# Filter_R.net
KiCad netlist of a schematic drawn in Altium Designer
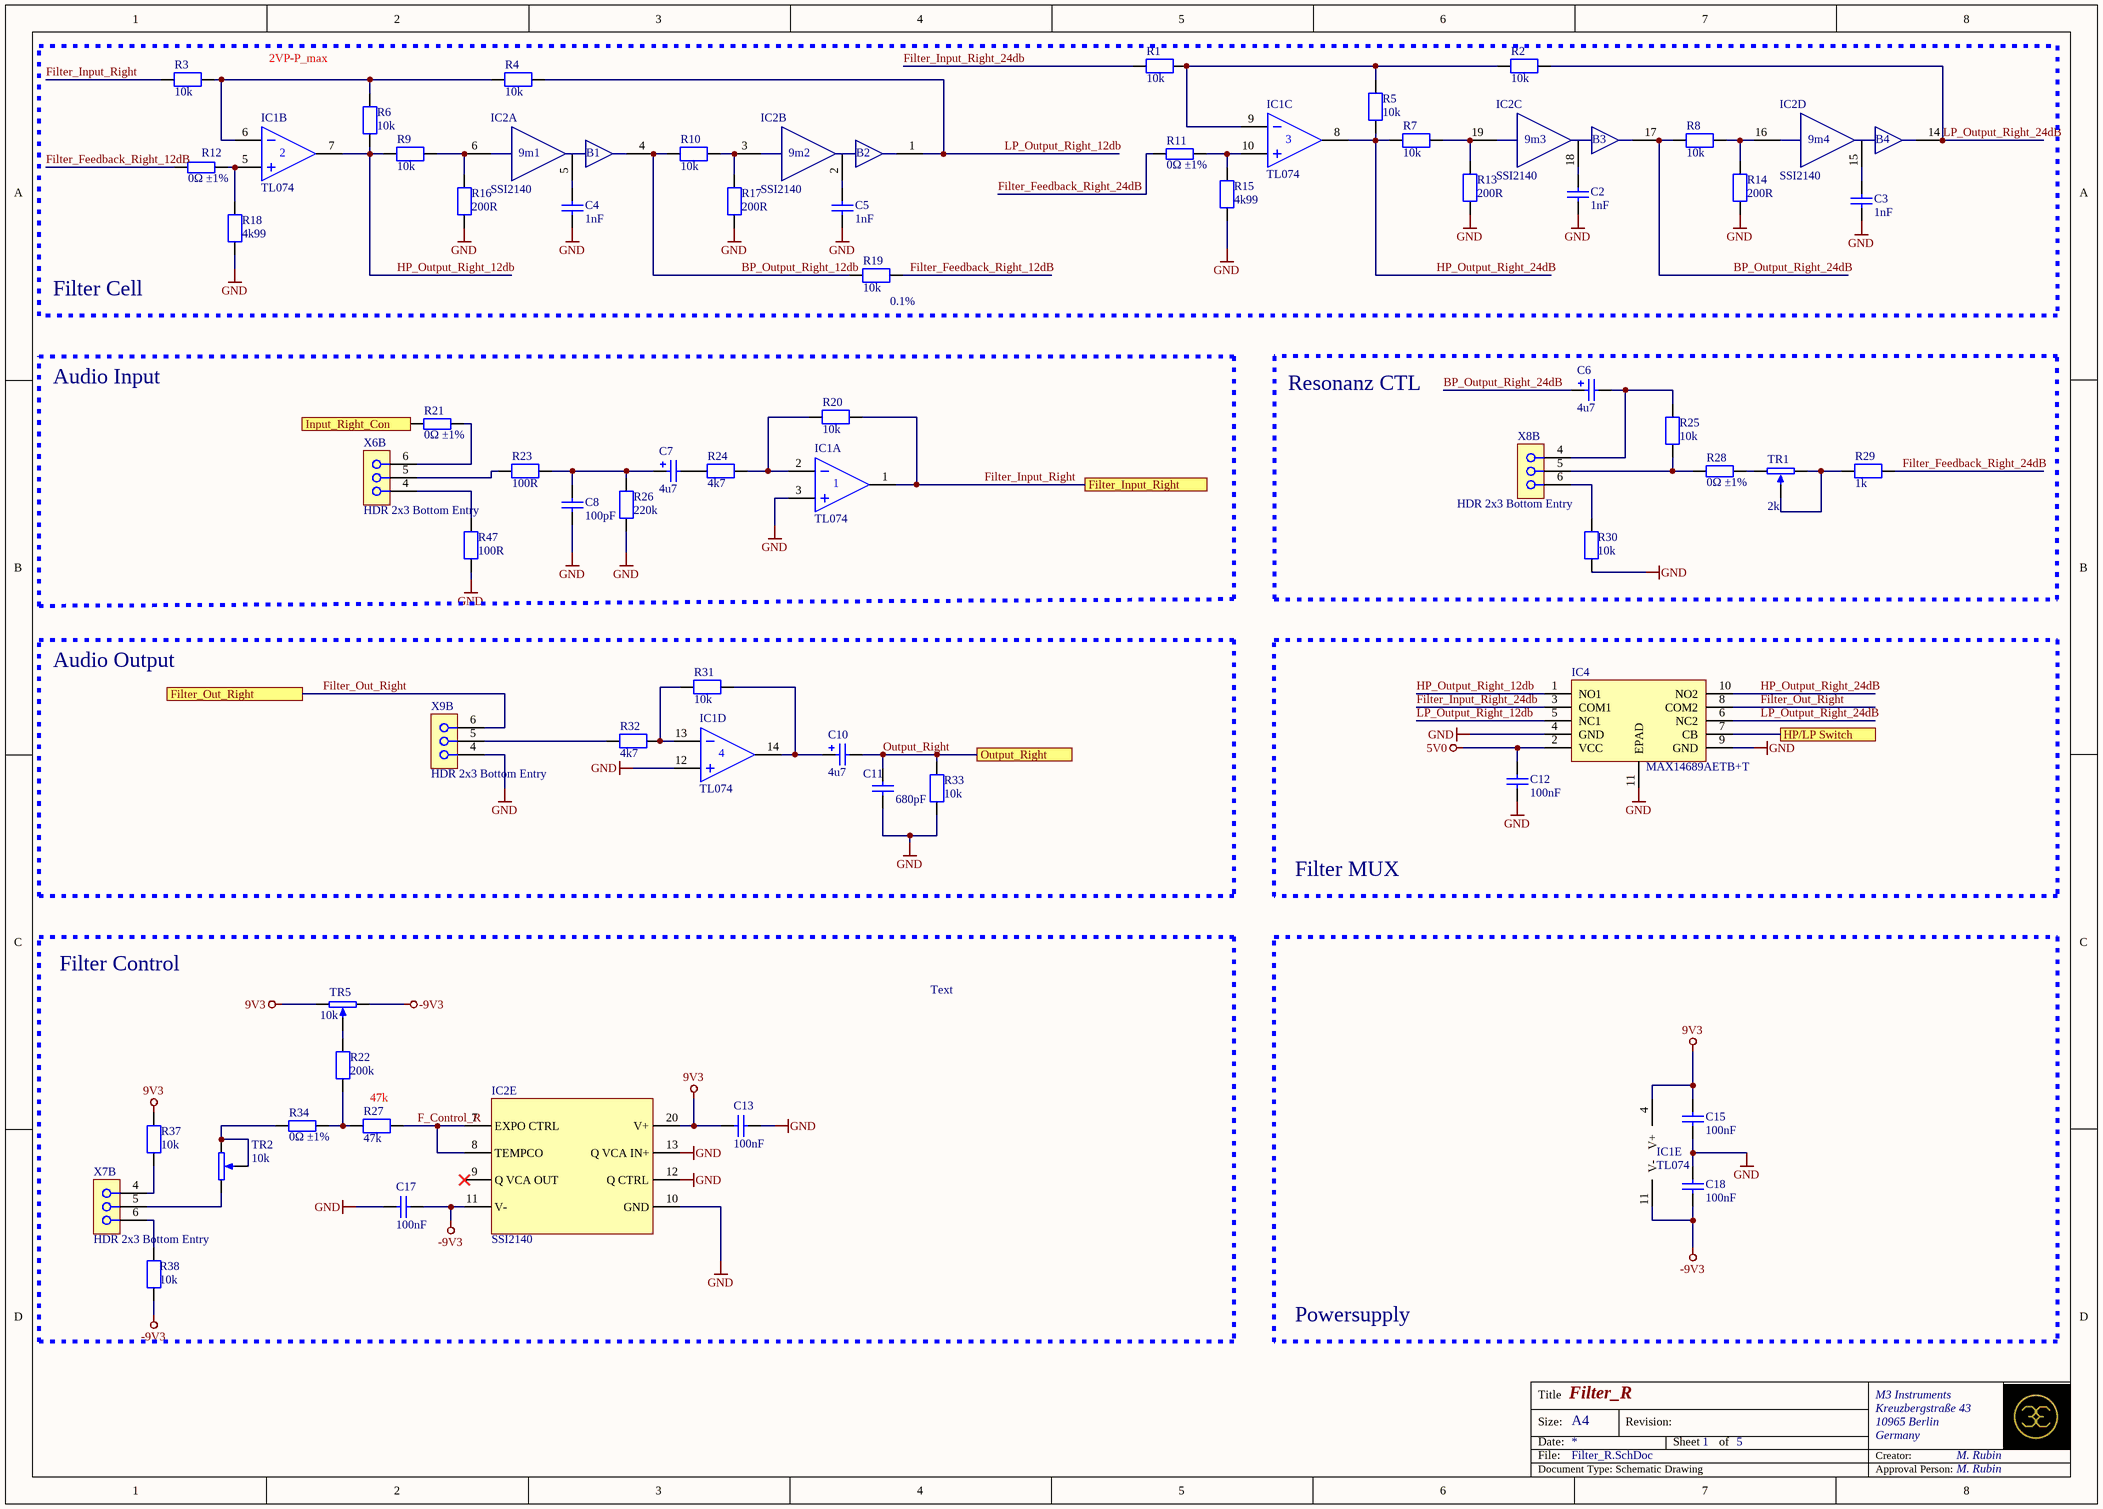
[diagram p0: Filter_R.SchDoc]

(export (version "E")
  (design (tool "Eeschema 10.0.6"))
  (components
    (comp (ref "C2")
      (value "1nF")
      (footprint "CAPC2012X145N")
      (description "Multilayer Ceramic Capacitors MLCC - SMD/SMT, C0G(NP0), 100nF")
      (fields
        (field (name "MANUFACTURER") "Murata Electronics")
        (field (name "MANUFACTURER PART NUMBER") "GRM21B5C2J102JWA3L")
      )
      (libsource (lib "Caps") (part "CAP_1nF_630V"))
    )
    (comp (ref "C3")
      (value "1nF")
      (footprint "CAPC2012X145N")
      (description "Multilayer Ceramic Capacitors MLCC - SMD/SMT, C0G(NP0), 1nF")
      (fields
        (field (name "MANUFACTURER") "Murata Electronics")
        (field (name "MANUFACTURER PART NUMBER") "GRM21B5C2J102JWA3L")
      )
      (libsource (lib "Caps") (part "CAP_100nF_630V"))
    )
    (comp (ref "C4")
      (value "1nF")
      (footprint "CAPC2012X145N")
      (description "Multilayer Ceramic Capacitors MLCC - SMD/SMT, C0G(NP0), 100nF")
      (fields
        (field (name "MANUFACTURER") "Murata Electronics")
        (field (name "MANUFACTURER PART NUMBER") "GRM21B5C2J102JWA3L")
      )
      (libsource (lib "Caps") (part "CAP_1nF_630V"))
    )
    (comp (ref "C5")
      (value "1nF")
      (footprint "CAPC2012X145N")
      (description "Multilayer Ceramic Capacitors MLCC - SMD/SMT, C0G(NP0), 1nF")
      (fields
        (field (name "MANUFACTURER") "Murata Electronics")
        (field (name "MANUFACTURER PART NUMBER") "GRM21B5C2J102JWA3L")
      )
      (libsource (lib "Caps") (part "CAP_100nF_630V"))
    )
    (comp (ref "C6")
      (value "4u7")
      (footprint "CAPAE4643X54M")
      (description "Aluminium Electrolytic Capacitors - SMD 4.7UF 16V ELECT VS BI-POLAR")
      (fields
        (field (name "MANUFACTURER") "Panasonic")
        (field (name "MANUFACTURER PART NUMBER") "EEE-1CA4R7NR")
      )
      (libsource (lib "Caps") (part "CAP_4u7"))
    )
    (comp (ref "C7")
      (value "4u7")
      (footprint "CAPAE4643X54M")
      (description "Aluminium Electrolytic Capacitors - SMD 4.7UF 16V ELECT VS BI-POLAR")
      (fields
        (field (name "MANUFACTURER") "Panasonic")
        (field (name "MANUFACTURER PART NUMBER") "EEE-1CA4R7NR")
      )
      (libsource (lib "Caps") (part "CAP_4u7"))
    )
    (comp (ref "C8")
      (value "100pF")
      (footprint "CAPC2012X145N")
      (description "Film Capacitors 100pF 50VDC 2% PPS FILM 0805")
      (fields
        (field (name "MANUFACTURER") "Panasonic")
        (field (name "MANUFACTURER PART NUMBER") "ECH-U1H101GX5")
      )
      (libsource (lib "Caps") (part "CAP_100pF_0805"))
    )
    (comp (ref "C10")
      (value "4u7")
      (footprint "CAPAE4643X54M")
      (description "Aluminium Electrolytic Capacitors - SMD 4.7UF 16V ELECT VS BI-POLAR")
      (fields
        (field (name "MANUFACTURER") "Panasonic")
        (field (name "MANUFACTURER PART NUMBER") "EEE-1CA4R7NR")
      )
      (libsource (lib "Caps") (part "CAP_4u7"))
    )
    (comp (ref "C11")
      (value "680pF")
      (footprint "CAPC2012X145N")
      (description "Film Capacitors 680pF 50VDC 2% PPS FILM 0805")
      (fields
        (field (name "MANUFACTURER") "Panasonic")
        (field (name "MANUFACTURER PART NUMBER") "ECH-U1H681GX5")
      )
      (libsource (lib "Caps") (part "CAP_680pF_0805"))
    )
    (comp (ref "C12")
      (value "100nF")
      (footprint "CAPC1608X95N")
      (description "Multilayer Ceramic Capacitors MLCC - SMD/SMT, 100nF")
      (fields
        (field (name "MANUFACTURER") "YAGEO")
        (field (name "MANUFACTURER PART NUMBER") "CC0603KRX7R9BB104")
      )
      (libsource (lib "Caps") (part "CAP_100nF_0603"))
    )
    (comp (ref "C13")
      (value "100nF")
      (footprint "CAPC1608X95N")
      (description "Multilayer Ceramic Capacitors MLCC - SMD/SMT, 100nF")
      (fields
        (field (name "MANUFACTURER") "YAGEO")
        (field (name "MANUFACTURER PART NUMBER") "CC0603KRX7R9BB104")
      )
      (libsource (lib "Caps") (part "CAP_100nF_0603"))
    )
    (comp (ref "C15")
      (value "100nF")
      (footprint "CAPC1608X95N")
      (description "Multilayer Ceramic Capacitors MLCC - SMD/SMT, 100nF")
      (fields
        (field (name "MANUFACTURER") "YAGEO")
        (field (name "MANUFACTURER PART NUMBER") "CC0603KRX7R9BB104")
      )
      (libsource (lib "Caps") (part "CAP_100nF_0603"))
    )
    (comp (ref "C17")
      (value "100nF")
      (footprint "CAPC1608X95N")
      (description "Multilayer Ceramic Capacitors MLCC - SMD/SMT, 100nF")
      (fields
        (field (name "MANUFACTURER") "YAGEO")
        (field (name "MANUFACTURER PART NUMBER") "CC0603KRX7R9BB104")
      )
      (libsource (lib "Caps") (part "CAP_100nF_0603"))
    )
    (comp (ref "C18")
      (value "100nF")
      (footprint "CAPC1608X95N")
      (description "Multilayer Ceramic Capacitors MLCC - SMD/SMT, 100nF")
      (fields
        (field (name "MANUFACTURER") "YAGEO")
        (field (name "MANUFACTURER PART NUMBER") "CC0603KRX7R9BB104")
      )
      (libsource (lib "Caps") (part "CAP_100nF_0603"))
    )
    (comp (ref "IC1")
      (value "TL074")
      (footprint "SOIC127P600X175-14N")
      (description "Operational Amplifiers - Op Amps Dual JFET Op Amp")
      (fields
        (field (name "MANUFACTURER") "Texas Instruments")
        (field (name "MANUFACTURER PART NUMBER") "TL074CDR")
      )
      (libsource (lib "ICs") (part "IC_TL074"))
    )
    (comp (ref "IC2")
      (value "SSI2140")
      (footprint "SOP65P650-20N")
      (description "Voltage Controlled Multi-Mode Filter")
      (fields (field (name "MANUFACTURER") "Sound Semiconductor"))
      (libsource (lib "ICs") (part "IC_SSI2140"))
    )
    (comp (ref "IC4")
      (value "MAX14689AETB+T")
      (footprint "QFN40P200X250X80_HS-11N")
      (description "Analogue Switch ICs Ultra-Small, Low-RON, Beyond-the-Rails™, DPDT Analog Switches")
      (fields (field (name "MANUFACTURER") "Maxim Integrated"))
      (libsource (lib "ICs") (part "IC_MAX14689AETB+T"))
    )
    (comp (ref "R1")
      (value "10k")
      (footprint "RESC2012X70N")
      (description "Thick Film Resistors - SMD 1/8watt 10Kohms 1% 100ppm")
      (fields
        (field (name "MANUFACTURER") "Vishay / Dale")
        (field (name "MANUFACTURER PART NUMBER") "CRCW080510K0FKEA")
      )
      (libsource (lib "") (part "RES_10k_0805_2"))
    )
    (comp (ref "R2")
      (value "10k")
      (footprint "RESC2012X70N")
      (description "Thick Film Resistors - SMD 1/8watt 10Kohms 1% 100ppm")
      (fields
        (field (name "MANUFACTURER") "Vishay / Dale")
        (field (name "MANUFACTURER PART NUMBER") "CRCW080510K0FKEA")
      )
      (libsource (lib "Resistors") (part "RES_10k_0805"))
    )
    (comp (ref "R3")
      (value "10k")
      (footprint "RESC2012X70N")
      (description "Thick Film Resistors - SMD 1/8watt 10Kohms 1% 100ppm")
      (fields
        (field (name "MANUFACTURER") "Vishay / Dale")
        (field (name "MANUFACTURER PART NUMBER") "CRCW080510K0FKEA")
      )
      (libsource (lib "Resistors") (part "RES_10k_0805"))
    )
    (comp (ref "R4")
      (value "10k")
      (footprint "RESC2012X70N")
      (description "Thick Film Resistors - SMD 1/8watt 10Kohms 1% 100ppm")
      (fields
        (field (name "MANUFACTURER") "Vishay / Dale")
        (field (name "MANUFACTURER PART NUMBER") "CRCW080510K0FKEA")
      )
      (libsource (lib "Resistors") (part "RES_10k_0805"))
    )
    (comp (ref "R5")
      (value "10k")
      (footprint "RESC2012X70N")
      (description "Thick Film Resistors - SMD 1/8watt 10Kohms 1% 100ppm")
      (fields
        (field (name "MANUFACTURER") "Vishay / Dale")
        (field (name "MANUFACTURER PART NUMBER") "CRCW080510K0FKEA")
      )
      (libsource (lib "") (part "RES_10k_0805_1"))
    )
    (comp (ref "R6")
      (value "10k")
      (footprint "RESC2012X70N")
      (description "Thick Film Resistors - SMD 1/8watt 10Kohms 1% 100ppm")
      (fields
        (field (name "MANUFACTURER") "Vishay / Dale")
        (field (name "MANUFACTURER PART NUMBER") "CRCW080510K0FKEA")
      )
      (libsource (lib "") (part "RES_10k_0805_1"))
    )
    (comp (ref "R7")
      (value "10k")
      (footprint "RESC2012X70N")
      (description "Thick Film Resistors - SMD 1/8watt 10Kohms 1% 100ppm")
      (fields
        (field (name "MANUFACTURER") "Vishay / Dale")
        (field (name "MANUFACTURER PART NUMBER") "CRCW080510K0FKEA")
      )
      (libsource (lib "Resistors") (part "RES_10k_0805"))
    )
    (comp (ref "R8")
      (value "10k")
      (footprint "RESC2012X70N")
      (description "Thick Film Resistors - SMD 1/8watt 10Kohms 1% 100ppm")
      (fields
        (field (name "MANUFACTURER") "Vishay / Dale")
        (field (name "MANUFACTURER PART NUMBER") "CRCW080510K0FKEA")
      )
      (libsource (lib "Resistors") (part "RES_10k_0805"))
    )
    (comp (ref "R9")
      (value "10k")
      (footprint "RESC2012X70N")
      (description "Thick Film Resistors - SMD 1/8watt 10Kohms 1% 100ppm")
      (fields
        (field (name "MANUFACTURER") "Vishay / Dale")
        (field (name "MANUFACTURER PART NUMBER") "CRCW080510K0FKEA")
      )
      (libsource (lib "Resistors") (part "RES_10k_0805"))
    )
    (comp (ref "R10")
      (value "10k")
      (footprint "RESC2012X70N")
      (description "Thick Film Resistors - SMD 1/8watt 10Kohms 1% 100ppm")
      (fields
        (field (name "MANUFACTURER") "Vishay / Dale")
        (field (name "MANUFACTURER PART NUMBER") "CRCW080510K0FKEA")
      )
      (libsource (lib "Resistors") (part "RES_10k_0805"))
    )
    (comp (ref "R11")
      (value "0Ω ±1%")
      (footprint "RESC2012X70N")
      (description "Chip resistor")
      (fields (field (name "TOLERANCE") "1%") (field (name "MANUFACTURER PART NUMBER") "CRCW08050000Z0EAC"))
      (libsource (lib "Resistors") (part "0805 0R (0R0) 1%"))
    )
    (comp (ref "R12")
      (value "0Ω ±1%")
      (footprint "RESC2012X70N")
      (description "Chip resistor")
      (fields (field (name "TOLERANCE") "1%") (field (name "MANUFACTURER PART NUMBER") "CRCW08050000Z0EAC"))
      (libsource (lib "Resistors") (part "0805 0R (0R0) 1%"))
    )
    (comp (ref "R13")
      (value "200R")
      (footprint "RESC2012X70N")
      (description "Thick Film Resistors - SMD 1/8watt 200ohms 1% 100ppm")
      (fields
        (field (name "MANUFACTURER") "Vishay / Dale")
        (field (name "MANUFACTURER PART NUMBER") "CRCW0805200RFKEA")
      )
      (libsource (lib "Resistors") (part "RES_200R_0805"))
    )
    (comp (ref "R14")
      (value "200R")
      (footprint "RESC2012X70N")
      (description "Thick Film Resistors - SMD 1/8watt 200ohms 1% 100ppm")
      (fields
        (field (name "MANUFACTURER") "Vishay / Dale")
        (field (name "MANUFACTURER PART NUMBER") "CRCW0805200RFKEA")
      )
      (libsource (lib "Resistors") (part "RES_200R_0805"))
    )
    (comp (ref "R15")
      (value "4k99")
      (footprint "RESC2012X70N")
      (description "Thick Film Resistors - SMD 1/8watt 4.99Kohms 1% 100ppm")
      (fields
        (field (name "MANUFACTURER") "Vishay / Dale")
        (field (name "MANUFACTURER PART NUMBER") "CRCW08054K99FKEA")
      )
      (libsource (lib "Resistors") (part "RES_4k99_0805"))
    )
    (comp (ref "R16")
      (value "200R")
      (footprint "RESC2012X70N")
      (description "Thick Film Resistors - SMD 1/8watt 200ohms 1% 100ppm")
      (fields
        (field (name "MANUFACTURER") "Vishay / Dale")
        (field (name "MANUFACTURER PART NUMBER") "CRCW0805200RFKEA")
      )
      (libsource (lib "Resistors") (part "RES_200R_0805"))
    )
    (comp (ref "R17")
      (value "200R")
      (footprint "RESC2012X70N")
      (description "Thick Film Resistors - SMD 1/8watt 200ohms 1% 100ppm")
      (fields
        (field (name "MANUFACTURER") "Vishay / Dale")
        (field (name "MANUFACTURER PART NUMBER") "CRCW0805200RFKEA")
      )
      (libsource (lib "Resistors") (part "RES_200R_0805"))
    )
    (comp (ref "R18")
      (value "4k99")
      (footprint "RESC2012X70N")
      (description "Thick Film Resistors - SMD 1/8watt 4.99Kohms 1% 100ppm")
      (fields
        (field (name "MANUFACTURER") "Vishay / Dale")
        (field (name "MANUFACTURER PART NUMBER") "CRCW08054K99FKEA")
      )
      (libsource (lib "Resistors") (part "RES_4k99_0805"))
    )
    (comp (ref "R19")
      (value "10k")
      (footprint "RESC2012X70N")
      (description "Thick Film Resistors - SMD 1/8watt 10Kohms 1% 100ppm")
      (fields
        (field (name "MANUFACTURER") "Vishay / Dale")
        (field (name "MANUFACTURER PART NUMBER") "CRCW080510K0FKEA")
      )
      (libsource (lib "Resistors") (part "RES_10k_0805"))
    )
    (comp (ref "R20")
      (value "10k")
      (footprint "RESC2012X70N")
      (description "Thick Film Resistors - SMD 1/8watt 10Kohms 1% 100ppm")
      (fields
        (field (name "MANUFACTURER") "Vishay / Dale")
        (field (name "MANUFACTURER PART NUMBER") "CRCW080510K0FKEA")
      )
      (libsource (lib "") (part "RES_10k_0805_2"))
    )
    (comp (ref "R21")
      (value "0Ω ±1%")
      (footprint "RESC2012X70N")
      (description "Chip resistor")
      (fields (field (name "TOLERANCE") "1%") (field (name "MANUFACTURER PART NUMBER") "CRCW08050000Z0EAC"))
      (libsource (lib "Resistors") (part "0805 0R (0R0) 1%"))
    )
    (comp (ref "R22")
      (value "200k")
      (footprint "RESC2012X70N")
      (description "Thick Film Resistors - SMD 1/8watt 200Kohms 1%")
      (fields
        (field (name "MANUFACTURER") "Vishay / Dale")
        (field (name "MANUFACTURER PART NUMBER") "CRCW0805200KFKEA")
      )
      (libsource (lib "Resistors") (part "RES_200k_0805"))
    )
    (comp (ref "R23")
      (value "100R")
      (footprint "RESC2012X70N")
      (description "Thick Film Resistors 1/8watt 100ohms 1% 100ppm")
      (fields
        (field (name "MANUFACTURER") "Vishay / Dale")
        (field (name "MANUFACTURER PART NUMBER") "CRCW0805100RFKEA")
      )
      (libsource (lib "Resistors") (part "RES_100R_0805"))
    )
    (comp (ref "R24")
      (value "4k7")
      (footprint "RESC2012X70N")
      (description "Thick Film Resistors - SMD 1/8Watt 4.7Kohms 1% Commercial Use")
      (fields
        (field (name "MANUFACTURER") "Vishay / Dale")
        (field (name "MANUFACTURER PART NUMBER") "CRCW08054K70FKEAC")
      )
      (libsource (lib "Resistors") (part "RES_4k7_0805"))
    )
    (comp (ref "R25")
      (value "10k")
      (footprint "RESC2012X70N")
      (description "Thick Film Resistors - SMD 1/8watt 10Kohms 1% 100ppm")
      (fields
        (field (name "MANUFACTURER") "Vishay / Dale")
        (field (name "MANUFACTURER PART NUMBER") "CRCW080510K0FKEA")
      )
      (libsource (lib "") (part "RES_10k_0805_1"))
    )
    (comp (ref "R26")
      (value "220k")
      (footprint "RESC2012X70N")
      (description "Thick Film Resistors - SMD 1/8watt 220Kohms 1%")
      (fields
        (field (name "MANUFACTURER") "Vishay / Dale")
        (field (name "MANUFACTURER PART NUMBER") "CRCW0805220KFKEA")
      )
      (libsource (lib "Resistors") (part "RES_220k_0805"))
    )
    (comp (ref "R27")
      (value "47k")
      (footprint "RESC2012X70N")
      (description "Thick Film Resistors - SMD 1/8watt 47Kohms 1%")
      (fields
        (field (name "MANUFACTURER") "Vishay / Dale")
        (field (name "MANUFACTURER PART NUMBER") "CRCW080547K0FKEB")
      )
      (libsource (lib "Resistors") (part "RES_47k_0805"))
    )
    (comp (ref "R28")
      (value "0Ω ±1%")
      (footprint "RESC2012X70N")
      (description "Chip resistor")
      (fields (field (name "TOLERANCE") "1%") (field (name "MANUFACTURER PART NUMBER") "CRCW08050000Z0EAC"))
      (libsource (lib "Resistors") (part "0805 0R (0R0) 1%"))
    )
    (comp (ref "R29")
      (value "1k")
      (footprint "RESC2012X70N")
      (description "Thick Film Resistors - SMD 1/8watt 1Kohms 1% 100ppm")
      (fields
        (field (name "MANUFACTURER") "Vishay / Dale")
        (field (name "MANUFACTURER PART NUMBER") "CRCW08051K00FKEA")
      )
      (libsource (lib "Resistors") (part "RES_1k_0805"))
    )
    (comp (ref "R30")
      (value "10k")
      (footprint "RESC2012X70N")
      (description "Thick Film Resistors - SMD 1/8watt 10Kohms 1% 100ppm")
      (fields (field (name "TOLERANCE") "1%") (field (name "MANUFACTURER PART NUMBER") "CRCW080510K0FKEA"))
      (libsource (lib "") (part "RES_10k_0805_1"))
    )
    (comp (ref "R31")
      (value "10k")
      (footprint "RESC2012X70N")
      (description "Thick Film Resistors - SMD 1/8watt 10Kohms 1% 100ppm")
      (fields
        (field (name "MANUFACTURER") "Vishay / Dale")
        (field (name "MANUFACTURER PART NUMBER") "CRCW080510K0FKEA")
      )
      (libsource (lib "") (part "RES_10k_0805_2"))
    )
    (comp (ref "R32")
      (value "4k7")
      (footprint "RESC2012X70N")
      (description "Thick Film Resistors - SMD 1/8Watt 4.7Kohms 1% Commercial Use")
      (fields
        (field (name "MANUFACTURER") "Vishay / Dale")
        (field (name "MANUFACTURER PART NUMBER") "CRCW08054K70FKEAC")
      )
      (libsource (lib "Resistors") (part "RES_4k7_0805"))
    )
    (comp (ref "R33")
      (value "10k")
      (footprint "RESC2012X70N")
      (description "Thick Film Resistors - SMD 1/8watt 10Kohms 1% 100ppm")
      (fields
        (field (name "MANUFACTURER") "Vishay / Dale")
        (field (name "MANUFACTURER PART NUMBER") "CRCW080510K0FKEA")
      )
      (libsource (lib "") (part "RES_10k_0805_1"))
    )
    (comp (ref "R34")
      (value "0Ω ±1%")
      (footprint "RESC2012X70N")
      (description "Chip resistor")
      (fields (field (name "TOLERANCE") "1%") (field (name "MANUFACTURER PART NUMBER") "CRCW08050000Z0EAC"))
      (libsource (lib "Resistors") (part "0805 0R (0R0) 1%"))
    )
    (comp (ref "R37")
      (value "10k")
      (footprint "RESC2012X70N")
      (description "Thick Film Resistors - SMD 1/8watt 10Kohms 1% 100ppm")
      (fields
        (field (name "MANUFACTURER") "Vishay / Dale")
        (field (name "MANUFACTURER PART NUMBER") "CRCW080510K0FKEA")
      )
      (libsource (lib "") (part "RES_10k_0805_1"))
    )
    (comp (ref "R38")
      (value "10k")
      (footprint "RESC2012X70N")
      (description "Thick Film Resistors - SMD 1/8watt 10Kohms 1% 100ppm")
      (fields (field (name "TOLERANCE") "1%") (field (name "MANUFACTURER PART NUMBER") "CRCW080510K0FKEA"))
      (libsource (lib "") (part "RES_10k_0805_1"))
    )
    (comp (ref "R47")
      (value "100R")
      (footprint "RESC2012X70N")
      (description "Thick Film Resistors 1/8watt 100ohms 1% 100ppm")
      (fields
        (field (name "MANUFACTURER") "Vishay / Dale")
        (field (name "MANUFACTURER PART NUMBER") "CRCW0805100RFKEA")
      )
      (libsource (lib "") (part "RES_100R_0805_1"))
    )
    (comp (ref "TR1")
      (value "2k")
      (footprint "PVG3G503C01R00")
      (description "Trimmer Resistors - SMD 2.0Kohms Sealed 3mm Sngl turn")
      (fields
        (field (name "MANUFACTURER") "Bourns")
        (field (name "MANUFACTURER PART NUMBER") "PVG3A202C01R00")
      )
      (libsource (lib "Resistors") (part "TRIM_2k_lin"))
    )
    (comp (ref "TR2")
      (value "10k")
      (footprint "3296Y")
      (description "10 kOhms 0.5W, 1/2W PC Pins Through Hole Trimmer Potentiometer Cermet 25.0 Turn Top Adjustment")
      (fields
        (field (name "MANUFACTURER") "Bourns")
        (field (name "MANUFACTURER PART NUMBER") "3296Y-1-103LF")
      )
      (libsource (lib "") (part "TRIM_10k_lin_25_1"))
    )
    (comp (ref "TR5")
      (value "10k")
      (footprint "3296Y")
      (description "10 kOhms 0.5W, 1/2W PC Pins Through Hole Trimmer Potentiometer Cermet 25.0 Turn Top Adjustment")
      (fields
        (field (name "MANUFACTURER") "Bourns")
        (field (name "MANUFACTURER PART NUMBER") "3296Y-1-103LF")
      )
      (libsource (lib "Resistors") (part "TRIM_10k_lin_25"))
    )
    (comp (ref "X6")
      (value "HDR 2x3 Bottom Entry")
      (footprint "613006216921-poti")
      (fields (field (name "MANUFACTURER") "WE") (field (name "MANUFACTURER PART NUMBER") "613004216921"))
      (libsource (lib "Connectors") (part "CON_SOCKET_2x3_Poti"))
    )
    (comp (ref "X7")
      (value "HDR 2x3 Bottom Entry")
      (footprint "613006216921-poti")
      (fields (field (name "MANUFACTURER") "WE") (field (name "MANUFACTURER PART NUMBER") "613004216921"))
      (libsource (lib "") (part "CON_SOCKET_2x3_Poti_1"))
    )
    (comp (ref "X8")
      (value "HDR 2x3 Bottom Entry")
      (footprint "613006216921-poti")
      (fields (field (name "MANUFACTURER") "WE") (field (name "MANUFACTURER PART NUMBER") "613004216921"))
      (libsource (lib "") (part "CON_SOCKET_2x3_Poti_1"))
    )
    (comp (ref "X9")
      (value "HDR 2x3 Bottom Entry")
      (footprint "613006216921-poti")
      (fields (field (name "MANUFACTURER") "WE") (field (name "MANUFACTURER PART NUMBER") "613004216921"))
      (libsource (lib "Connectors") (part "CON_SOCKET_2x3_Poti"))
    )
  )
  (nets
    (net (code "1") (name "-9V3") (class "Default")
      (node (ref "C17") (pin "2") (pinfunction "2_2") (pintype "passive"))
      (node (ref "C18") (pin "1") (pinfunction "1_1") (pintype "passive"))
      (node (ref "IC1") (pin "11") (pinfunction "V-_11") (pintype "power_in"))
      (node (ref "IC2") (pin "11") (pinfunction "V-_11") (pintype "passive"))
      (node (ref "R38") (pin "1") (pinfunction "1_1") (pintype "passive"))
      (node (ref "TR5") (pin "3") (pinfunction "3_3") (pintype "passive"))
    )
    (net (code "2") (name "/BP_Output_Right_12db") (class "Default")
      (node (ref "IC2") (pin "4") (pinfunction "OUT_1_4") (pintype "passive"))
      (node (ref "R10") (pin "1") (pinfunction "1_1") (pintype "passive"))
      (node (ref "R19") (pin "1") (pinfunction "1_1") (pintype "passive"))
    )
    (net (code "3") (name "/BP_Output_Right_24dB") (class "Default")
      (node (ref "C6") (pin "1") (pinfunction "1_1") (pintype "passive"))
      (node (ref "IC2") (pin "17") (pinfunction "OUT_3_17") (pintype "passive"))
      (node (ref "R8") (pin "1") (pinfunction "1_1") (pintype "passive"))
    )
    (net (code "4") (name "/F_Control_R") (class "Default")
      (node (ref "IC2") (pin "7") (pinfunction "EXPO_CTRL_7") (pintype "passive"))
      (node (ref "IC2") (pin "8") (pinfunction "TEMPCO_8") (pintype "power_in"))
      (node (ref "R27") (pin "2") (pinfunction "2_2") (pintype "passive"))
    )
    (net (code "5") (name "/Filter_Feedback_Right_12dB") (class "Default")
      (node (ref "R12") (pin "1") (pinfunction "1_1") (pintype "passive"))
      (node (ref "R19") (pin "2") (pinfunction "2_2") (pintype "passive"))
    )
    (net (code "6") (name "/Filter_Feedback_Right_24dB") (class "Default")
      (node (ref "R11") (pin "1") (pinfunction "1_1") (pintype "passive"))
      (node (ref "R29") (pin "1") (pinfunction "1_1") (pintype "passive"))
    )
    (net (code "7") (name "/Filter_Input_Right") (class "Default")
      (node (ref "IC1") (pin "1") (pinfunction "OUT_1") (pintype "passive"))
      (node (ref "R20") (pin "1") (pinfunction "1_1") (pintype "passive"))
      (node (ref "R3") (pin "1") (pinfunction "1_1") (pintype "passive"))
    )
    (net (code "8") (name "/Filter_Input_Right_24db") (class "Default")
      (node (ref "IC4") (pin "3") (pinfunction "COM1_3") (pintype "passive"))
      (node (ref "R1") (pin "2") (pinfunction "2_2") (pintype "passive"))
    )
    (net (code "9") (name "/Filter_Out_Right") (class "Default")
      (node (ref "IC4") (pin "8") (pinfunction "COM2_8") (pintype "passive"))
      (node (ref "X9") (pin "6") (pinfunction "6_6") (pintype "passive"))
    )
    (net (code "10") (name "/HP_Output_Right_12db") (class "Default")
      (node (ref "IC1") (pin "7") (pinfunction "OUT_7") (pintype "passive"))
      (node (ref "IC4") (pin "1") (pinfunction "NO1_1") (pintype "passive"))
      (node (ref "R6") (pin "1") (pinfunction "1_1") (pintype "passive"))
      (node (ref "R9") (pin "1") (pinfunction "1_1") (pintype "passive"))
    )
    (net (code "11") (name "/HP_Output_Right_24dB") (class "Default")
      (node (ref "IC1") (pin "8") (pinfunction "OUT_8") (pintype "passive"))
      (node (ref "IC4") (pin "10") (pinfunction "NO2_10") (pintype "passive"))
      (node (ref "R5") (pin "1") (pinfunction "1_1") (pintype "passive"))
      (node (ref "R7") (pin "1") (pinfunction "1_1") (pintype "passive"))
    )
    (net (code "12") (name "/HP{slash}LP Switch") (class "Default")
      (node (ref "IC4") (pin "7") (pinfunction "CB_7") (pintype "passive"))
    )
    (net (code "13") (name "/Input_Right_Con") (class "Default")
      (node (ref "R21") (pin "1") (pinfunction "1_1") (pintype "passive"))
    )
    (net (code "14") (name "/LP_Output_Right_12db") (class "Default")
      (node (ref "IC2") (pin "1") (pinfunction "OUT_2_1") (pintype "passive"))
      (node (ref "IC4") (pin "5") (pinfunction "NC1_5") (pintype "passive"))
      (node (ref "R4") (pin "2") (pinfunction "2_2") (pintype "passive"))
    )
    (net (code "15") (name "/LP_Output_Right_24dB") (class "Default")
      (node (ref "IC2") (pin "14") (pinfunction "OUT_4_14") (pintype "passive"))
      (node (ref "IC4") (pin "6") (pinfunction "NC2_6") (pintype "passive"))
      (node (ref "R2") (pin "2") (pinfunction "2_2") (pintype "passive"))
    )
    (net (code "16") (name "/Output_Right") (class "Default")
      (node (ref "C10") (pin "2") (pinfunction "2_2") (pintype "passive"))
      (node (ref "C11") (pin "2") (pinfunction "2_2") (pintype "passive"))
      (node (ref "R33") (pin "2") (pinfunction "2_2") (pintype "passive"))
    )
    (net (code "17") (name "5V0") (class "Default")
      (node (ref "C12") (pin "2") (pinfunction "2_2") (pintype "passive"))
      (node (ref "IC4") (pin "2") (pinfunction "VCC_2") (pintype "passive"))
    )
    (net (code "18") (name "9V3") (class "Default")
      (node (ref "C13") (pin "1") (pinfunction "1_1") (pintype "passive"))
      (node (ref "C15") (pin "2") (pinfunction "2_2") (pintype "passive"))
      (node (ref "IC1") (pin "4") (pinfunction "V+_4") (pintype "power_in"))
      (node (ref "IC2") (pin "20") (pinfunction "V+_20") (pintype "passive"))
      (node (ref "R37") (pin "2") (pinfunction "2_2") (pintype "passive"))
      (node (ref "TR5") (pin "1") (pinfunction "1_1") (pintype "passive"))
    )
    (net (code "19") (name "GND") (class "Default")
      (node (ref "C11") (pin "1") (pinfunction "1_1") (pintype "passive"))
      (node (ref "C12") (pin "1") (pinfunction "1_1") (pintype "passive"))
      (node (ref "C13") (pin "2") (pinfunction "2_2") (pintype "passive"))
      (node (ref "C15") (pin "1") (pinfunction "1_1") (pintype "passive"))
      (node (ref "C17") (pin "1") (pinfunction "1_1") (pintype "passive"))
      (node (ref "C18") (pin "2") (pinfunction "2_2") (pintype "passive"))
      (node (ref "C2") (pin "1") (pinfunction "1_1") (pintype "passive"))
      (node (ref "C3") (pin "1") (pinfunction "1_1") (pintype "passive"))
      (node (ref "C4") (pin "1") (pinfunction "1_1") (pintype "passive"))
      (node (ref "C5") (pin "1") (pinfunction "1_1") (pintype "passive"))
      (node (ref "C8") (pin "1") (pinfunction "1_1") (pintype "passive"))
      (node (ref "IC1") (pin "12") (pinfunction "IN+_12") (pintype "passive"))
      (node (ref "IC1") (pin "3") (pinfunction "IN+_3") (pintype "passive"))
      (node (ref "IC2") (pin "10") (pinfunction "GND_10") (pintype "passive"))
      (node (ref "IC2") (pin "12") (pinfunction "Q_CTRL_12") (pintype "power_in"))
      (node (ref "IC2") (pin "13") (pinfunction "Q_VCA_IN+_13") (pintype "power_in"))
      (node (ref "IC4") (pin "11") (pinfunction "EPAD_11") (pintype "passive"))
      (node (ref "IC4") (pin "4") (pinfunction "GND_4") (pintype "passive"))
      (node (ref "IC4") (pin "9") (pinfunction "GND_9") (pintype "passive"))
      (node (ref "R13") (pin "1") (pinfunction "1_1") (pintype "passive"))
      (node (ref "R14") (pin "1") (pinfunction "1_1") (pintype "passive"))
      (node (ref "R15") (pin "1") (pinfunction "1_1") (pintype "passive"))
      (node (ref "R16") (pin "1") (pinfunction "1_1") (pintype "passive"))
      (node (ref "R17") (pin "1") (pinfunction "1_1") (pintype "passive"))
      (node (ref "R18") (pin "1") (pinfunction "1_1") (pintype "passive"))
      (node (ref "R26") (pin "1") (pinfunction "1_1") (pintype "passive"))
      (node (ref "R30") (pin "1") (pinfunction "1_1") (pintype "passive"))
      (node (ref "R33") (pin "1") (pinfunction "1_1") (pintype "passive"))
      (node (ref "R47") (pin "1") (pinfunction "1_1") (pintype "passive"))
      (node (ref "X9") (pin "4") (pinfunction "4_4") (pintype "passive"))
    )
    (net (code "20") (name "Net-(C6-Pad2)") (class "Default")
      (node (ref "C6") (pin "2") (pinfunction "2_2") (pintype "passive"))
      (node (ref "R25") (pin "2") (pinfunction "2_2") (pintype "passive"))
      (node (ref "X8") (pin "4") (pinfunction "4_4") (pintype "passive"))
    )
    (net (code "21") (name "Net-(C7-Pad1)") (class "Default")
      (node (ref "C7") (pin "1") (pinfunction "1_1") (pintype "passive"))
      (node (ref "C8") (pin "2") (pinfunction "2_2") (pintype "passive"))
      (node (ref "R23") (pin "2") (pinfunction "2_2") (pintype "passive"))
      (node (ref "R26") (pin "2") (pinfunction "2_2") (pintype "passive"))
    )
    (net (code "22") (name "Net-(C7-Pad2)") (class "Default")
      (node (ref "C7") (pin "2") (pinfunction "2_2") (pintype "passive"))
      (node (ref "R24") (pin "2") (pinfunction "2_2") (pintype "passive"))
    )
    (net (code "23") (name "Net-(IC1A-IN-)") (class "Default")
      (node (ref "IC1") (pin "2") (pinfunction "IN-_2") (pintype "passive"))
      (node (ref "R20") (pin "2") (pinfunction "2_2") (pintype "passive"))
      (node (ref "R24") (pin "1") (pinfunction "1_1") (pintype "passive"))
    )
    (net (code "24") (name "Net-(IC1B-IN+)") (class "Default")
      (node (ref "IC1") (pin "5") (pinfunction "IN+_5") (pintype "passive"))
      (node (ref "R12") (pin "2") (pinfunction "2_2") (pintype "passive"))
      (node (ref "R18") (pin "2") (pinfunction "2_2") (pintype "passive"))
    )
    (net (code "25") (name "Net-(IC1B-IN-)") (class "Default")
      (node (ref "IC1") (pin "6") (pinfunction "IN-_6") (pintype "passive"))
      (node (ref "R3") (pin "2") (pinfunction "2_2") (pintype "passive"))
      (node (ref "R4") (pin "1") (pinfunction "1_1") (pintype "passive"))
      (node (ref "R6") (pin "2") (pinfunction "2_2") (pintype "passive"))
    )
    (net (code "26") (name "Net-(IC1C-IN+)") (class "Default")
      (node (ref "IC1") (pin "9") (pinfunction "IN+_9") (pintype "passive"))
      (node (ref "R1") (pin "1") (pinfunction "1_1") (pintype "passive"))
      (node (ref "R2") (pin "1") (pinfunction "1_1") (pintype "passive"))
      (node (ref "R5") (pin "2") (pinfunction "2_2") (pintype "passive"))
    )
    (net (code "27") (name "Net-(IC1C-IN-)") (class "Default")
      (node (ref "IC1") (pin "10") (pinfunction "IN-_10") (pintype "passive"))
      (node (ref "R11") (pin "2") (pinfunction "2_2") (pintype "passive"))
      (node (ref "R15") (pin "2") (pinfunction "2_2") (pintype "passive"))
    )
    (net (code "28") (name "Net-(IC1D-IN-)") (class "Default")
      (node (ref "IC1") (pin "13") (pinfunction "IN-_13") (pintype "passive"))
      (node (ref "R31") (pin "2") (pinfunction "2_2") (pintype "passive"))
      (node (ref "R32") (pin "1") (pinfunction "1_1") (pintype "passive"))
    )
    (net (code "29") (name "Net-(IC1D-OUT)") (class "Default")
      (node (ref "C10") (pin "1") (pinfunction "1_1") (pintype "passive"))
      (node (ref "IC1") (pin "14") (pinfunction "OUT_14") (pintype "passive"))
      (node (ref "R31") (pin "1") (pinfunction "1_1") (pintype "passive"))
    )
    (net (code "30") (name "Net-(IC2A-CAP_1)") (class "Default")
      (node (ref "C4") (pin "2") (pinfunction "2_2") (pintype "passive"))
      (node (ref "IC2") (pin "5") (pinfunction "CAP_1_5") (pintype "passive"))
    )
    (net (code "31") (name "Net-(IC2A-IN_1)") (class "Default")
      (node (ref "IC2") (pin "6") (pinfunction "IN_1_6") (pintype "passive"))
      (node (ref "R16") (pin "2") (pinfunction "2_2") (pintype "passive"))
      (node (ref "R9") (pin "2") (pinfunction "2_2") (pintype "passive"))
    )
    (net (code "32") (name "Net-(IC2B-CAP_2)") (class "Default")
      (node (ref "C5") (pin "2") (pinfunction "2_2") (pintype "passive"))
      (node (ref "IC2") (pin "2") (pinfunction "CAP_2_2") (pintype "power_in"))
    )
    (net (code "33") (name "Net-(IC2B-IN_2)") (class "Default")
      (node (ref "IC2") (pin "3") (pinfunction "IN_2_3") (pintype "power_in"))
      (node (ref "R10") (pin "2") (pinfunction "2_2") (pintype "passive"))
      (node (ref "R17") (pin "2") (pinfunction "2_2") (pintype "passive"))
    )
    (net (code "34") (name "Net-(IC2C-CAP_3)") (class "Default")
      (node (ref "C2") (pin "2") (pinfunction "2_2") (pintype "passive"))
      (node (ref "IC2") (pin "18") (pinfunction "CAP_3_18") (pintype "power_in"))
    )
    (net (code "35") (name "Net-(IC2C-IN_3)") (class "Default")
      (node (ref "IC2") (pin "19") (pinfunction "IN_3_19") (pintype "passive"))
      (node (ref "R13") (pin "2") (pinfunction "2_2") (pintype "passive"))
      (node (ref "R7") (pin "2") (pinfunction "2_2") (pintype "passive"))
    )
    (net (code "36") (name "Net-(IC2D-CAP_4)") (class "Default")
      (node (ref "C3") (pin "2") (pinfunction "2_2") (pintype "passive"))
      (node (ref "IC2") (pin "15") (pinfunction "CAP_4_15") (pintype "passive"))
    )
    (net (code "37") (name "Net-(IC2D-IN_4)") (class "Default")
      (node (ref "IC2") (pin "16") (pinfunction "IN_4_16") (pintype "passive"))
      (node (ref "R14") (pin "2") (pinfunction "2_2") (pintype "passive"))
      (node (ref "R8") (pin "2") (pinfunction "2_2") (pintype "passive"))
    )
    (net (code "38") (name "Net-(R21-Pad2)") (class "Default")
      (node (ref "R21") (pin "2") (pinfunction "2_2") (pintype "passive"))
      (node (ref "X6") (pin "6") (pinfunction "6_6") (pintype "passive"))
    )
    (net (code "39") (name "Net-(R22-Pad1)") (class "Default")
      (node (ref "R22") (pin "1") (pinfunction "1_1") (pintype "passive"))
      (node (ref "R27") (pin "1") (pinfunction "1_1") (pintype "passive"))
      (node (ref "R34") (pin "2") (pinfunction "2_2") (pintype "passive"))
    )
    (net (code "40") (name "Net-(R22-Pad2)") (class "Default")
      (node (ref "R22") (pin "2") (pinfunction "2_2") (pintype "passive"))
      (node (ref "TR5") (pin "2") (pinfunction "2_2") (pintype "passive"))
    )
    (net (code "41") (name "Net-(R23-Pad1)") (class "Default")
      (node (ref "R23") (pin "1") (pinfunction "1_1") (pintype "passive"))
      (node (ref "X6") (pin "5") (pinfunction "5_5") (pintype "passive"))
    )
    (net (code "42") (name "Net-(R25-Pad1)") (class "Default")
      (node (ref "R25") (pin "1") (pinfunction "1_1") (pintype "passive"))
      (node (ref "R28") (pin "1") (pinfunction "1_1") (pintype "passive"))
      (node (ref "X8") (pin "5") (pinfunction "5_5") (pintype "passive"))
    )
    (net (code "43") (name "Net-(R28-Pad2)") (class "Default")
      (node (ref "R28") (pin "2") (pinfunction "2_2") (pintype "passive"))
      (node (ref "TR1") (pin "1") (pinfunction "1_1") (pintype "passive"))
    )
    (net (code "44") (name "Net-(R29-Pad2)") (class "Default")
      (node (ref "R29") (pin "2") (pinfunction "2_2") (pintype "passive"))
      (node (ref "TR1") (pin "2") (pinfunction "2_2") (pintype "passive"))
      (node (ref "TR1") (pin "3") (pinfunction "3_3") (pintype "passive"))
    )
    (net (code "45") (name "Net-(R30-Pad2)") (class "Default")
      (node (ref "R30") (pin "2") (pinfunction "2_2") (pintype "passive"))
      (node (ref "X8") (pin "6") (pinfunction "6_6") (pintype "passive"))
    )
    (net (code "46") (name "Net-(R32-Pad2)") (class "Default")
      (node (ref "R32") (pin "2") (pinfunction "2_2") (pintype "passive"))
      (node (ref "X9") (pin "5") (pinfunction "5_5") (pintype "passive"))
    )
    (net (code "47") (name "Net-(R34-Pad1)") (class "Default")
      (node (ref "R34") (pin "1") (pinfunction "1_1") (pintype "passive"))
      (node (ref "TR2") (pin "2") (pinfunction "2_2") (pintype "passive"))
      (node (ref "TR2") (pin "3") (pinfunction "3_3") (pintype "passive"))
    )
    (net (code "48") (name "Net-(R37-Pad1)") (class "Default")
      (node (ref "R37") (pin "1") (pinfunction "1_1") (pintype "passive"))
      (node (ref "X7") (pin "4") (pinfunction "4_4") (pintype "passive"))
    )
    (net (code "49") (name "Net-(R38-Pad2)") (class "Default")
      (node (ref "R38") (pin "2") (pinfunction "2_2") (pintype "passive"))
      (node (ref "X7") (pin "6") (pinfunction "6_6") (pintype "passive"))
    )
    (net (code "50") (name "Net-(R47-Pad2)") (class "Default")
      (node (ref "R47") (pin "2") (pinfunction "2_2") (pintype "passive"))
      (node (ref "X6") (pin "4") (pinfunction "4_4") (pintype "passive"))
    )
    (net (code "51") (name "Net-(TR2-Pad1)") (class "Default")
      (node (ref "TR2") (pin "1") (pinfunction "1_1") (pintype "passive"))
      (node (ref "X7") (pin "5") (pinfunction "5_5") (pintype "passive"))
    )
    (net (code "52") (name "unconnected-(IC2E-Q_VCA_OUT-Pad9)") (class "Default")
      (node (ref "IC2") (pin "9") (pinfunction "Q_VCA_OUT_9") (pintype "passive+no_connect"))
    )
  )
)
